# bluetooth_version_2.net
KiCad netlist of a schematic drawn in EAGLE
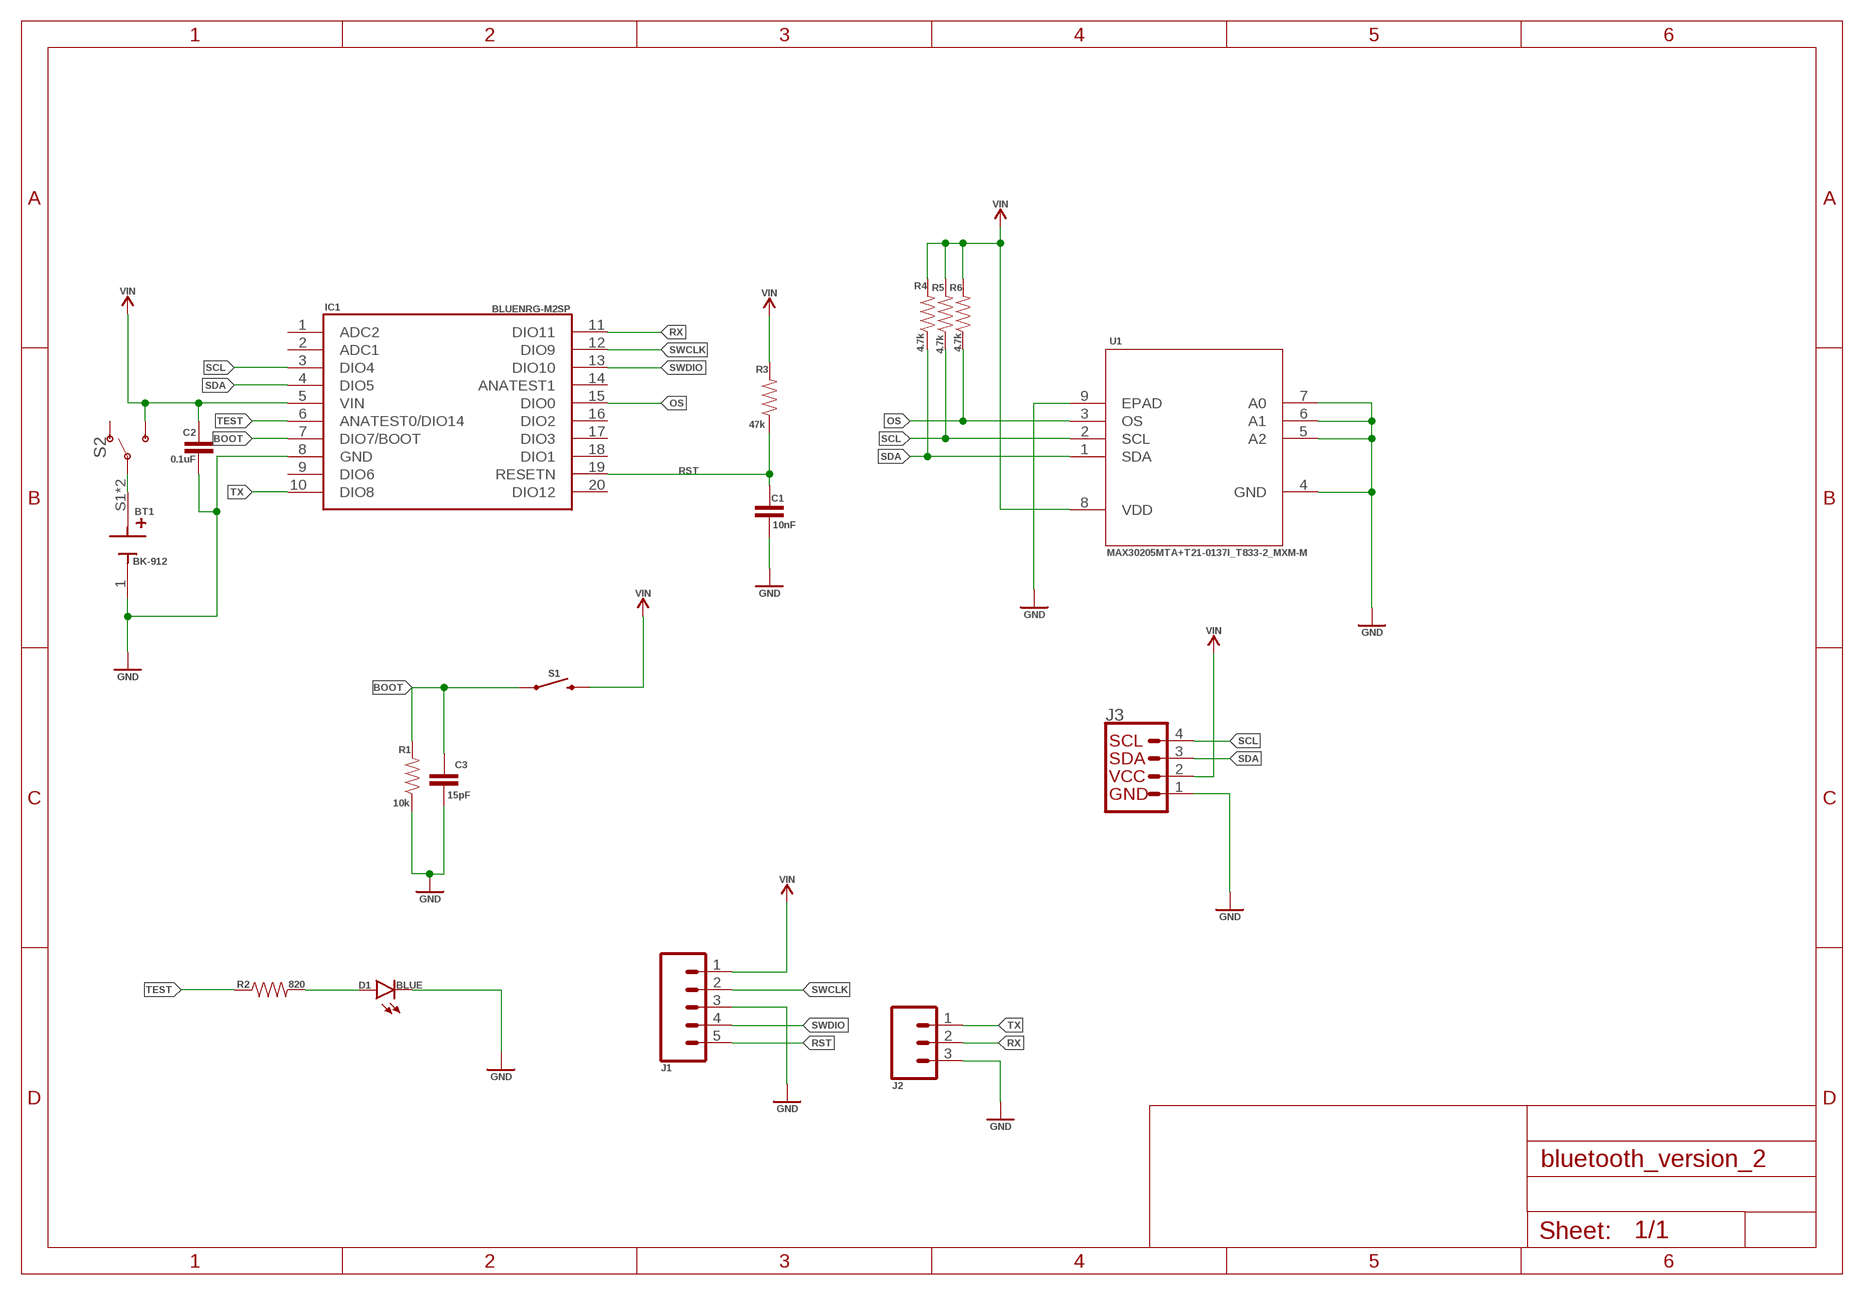
[diagram p0: schematic, sheet 1]

(export (version "E")
  (design (tool "Eeschema 10.0.6"))
  (components
    (comp (ref "BT1")
      (value "BK-912")
      (footprint "eagle-import:BAT_BK-912")
      (fields (field (name "MF") "MPD (Memory"))
      (libsource (lib "eagle-import") (part "BK-912"))
    )
    (comp (ref "C1")
      (value "10nF")
      (footprint "eagle-import:0603")
      (libsource (lib "eagle-import") (part "10NF-0603-50V-10%"))
    )
    (comp (ref "C2")
      (value "0.1uF")
      (footprint "eagle-import:0603")
      (libsource (lib "eagle-import") (part "0.1UF-0603-25V-(+80/-20%)"))
    )
    (comp (ref "C3")
      (value "15pF")
      (footprint "eagle-import:0603")
      (libsource (lib "eagle-import") (part "15PF-0603-50V-5%"))
    )
    (comp (ref "D1")
      (value "BLUE")
      (footprint "eagle-import:LED-0603")
      (libsource (lib "eagle-import") (part "LED-BLUE0603"))
    )
    (comp (ref "IC1")
      (value "BLUENRG-M2SP")
      (footprint "eagle-import:BLUENRGM2SP")
      (fields (field (name "MOUSER_PART_NUMBER") "511-BLUENRG-M2SP"))
      (libsource (lib "eagle-import") (part "BLUENRG-M2SP"))
    )
    (comp (ref "J1")
      (value "CONN_05")
      (footprint "eagle-import:1X05")
      (libsource (lib "eagle-import") (part "CONN_05"))
    )
    (comp (ref "J2")
      (value "455-1750-1-ND")
      (footprint "eagle-import:1X03")
      (libsource (lib "eagle-import") (part "CONN_03"))
    )
    (comp (ref "J3")
      (value "I2C_STANDARD")
      (footprint "eagle-import:1X04")
      (libsource (lib "eagle-import") (part "I2C_STANDARD"))
    )
    (comp (ref "R1")
      (value "10k")
      (footprint "eagle-import:0603")
      (libsource (lib "eagle-import") (part "10KOHM-0603-1/10W-1%"))
    )
    (comp (ref "R2")
      (value "820")
      (footprint "eagle-import:0603")
      (fields (field (name "SPICEPREFIX") "R"))
      (libsource (lib "eagle-import") (part "8.2KOHM-0603-1/10W-5%"))
    )
    (comp (ref "R3")
      (value "47k")
      (footprint "eagle-import:0603")
      (libsource (lib "eagle-import") (part "47KOHM-0603-1/10W-1%"))
    )
    (comp (ref "R4")
      (value "4.7k")
      (footprint "eagle-import:0603")
      (libsource (lib "eagle-import") (part "4.7KOHM-0603-1/10W-1%"))
    )
    (comp (ref "R5")
      (value "4.7k")
      (footprint "eagle-import:0603")
      (libsource (lib "eagle-import") (part "4.7KOHM-0603-1/10W-1%"))
    )
    (comp (ref "R6")
      (value "4.7k")
      (footprint "eagle-import:0603")
      (libsource (lib "eagle-import") (part "4.7KOHM-0603-1/10W-1%"))
    )
    (comp (ref "S1")
      (value "MOMENTARY-SWITCH-SPST-SMD-4.6X2.8MM")
      (footprint "eagle-import:TACTILE_SWITCH_SMD_4.6X2.8MM")
      (libsource (lib "eagle-import") (part "MOMENTARY-SWITCH-SPST-SMD-4.6X2.8MM"))
    )
    (comp (ref "S2")
      (value "SWITCH-SPDT-SMD-RIGHT-ANGLE")
      (footprint "eagle-import:SWITCH_SPST_SMD_A")
      (libsource (lib "eagle-import") (part "SWITCH-SPDT-SMD-RIGHT-ANGLE"))
    )
    (comp (ref "U1")
      (value "MAX30205MTA+T21-0137I_T833-2_MXM-M")
      (footprint "eagle-import:21-0137I_T833-2_MXM-M")
      (fields
        (field (name "MANUFACTURER_PART_NUMBER") "MAX30205MTA+T")
        (field (name "COPYRIGHT") "Copyright (C) 2018 Accelerated Designs. All rights reserved")
      )
      (libsource (lib "eagle-import") (part "MAX30205MTA+T21-0137I_T833-2_MXM-M"))
    )
  )
  (nets
    (net (code "1") (name "BOOT") (class "Default")
      (node (ref "C3") (pin "1") (pinfunction "1_1") (pintype "passive"))
      (node (ref "IC1") (pin "7") (pinfunction "DIO7/BOOT_7") (pintype "bidirectional"))
      (node (ref "R1") (pin "2") (pinfunction "2_2") (pintype "passive"))
      (node (ref "S1") (pin "1") (pinfunction "1_1") (pintype "passive"))
      (node (ref "S1") (pin "2") (pinfunction "1_2") (pintype "passive"))
    )
    (net (code "2") (name "GND") (class "Default")
      (node (ref "BT1") (pin "1") (pinfunction "-_1") (pintype "passive"))
      (node (ref "C1") (pin "2") (pinfunction "2_2") (pintype "passive"))
      (node (ref "C2") (pin "2") (pinfunction "2_2") (pintype "passive"))
      (node (ref "C3") (pin "2") (pinfunction "2_2") (pintype "passive"))
      (node (ref "D1") (pin "C") (pinfunction "C_C") (pintype "passive"))
      (node (ref "IC1") (pin "8") (pinfunction "GND_8") (pintype "bidirectional"))
      (node (ref "J1") (pin "3") (pinfunction "3_3") (pintype "passive"))
      (node (ref "J2") (pin "3") (pinfunction "3_3") (pintype "passive"))
      (node (ref "J3") (pin "1") (pinfunction "1_1") (pintype "power_in"))
      (node (ref "R1") (pin "1") (pinfunction "1_1") (pintype "passive"))
      (node (ref "U1") (pin "4") (pinfunction "GND_4") (pintype "passive"))
      (node (ref "U1") (pin "5") (pinfunction "A2_5") (pintype "bidirectional"))
      (node (ref "U1") (pin "6") (pinfunction "A1_6") (pintype "bidirectional"))
      (node (ref "U1") (pin "7") (pinfunction "A0_7") (pintype "bidirectional"))
      (node (ref "U1") (pin "9") (pinfunction "EPAD_9") (pintype "passive"))
    )
    (net (code "3") (name "Net-(D1-PadA)") (class "Default")
      (node (ref "D1") (pin "A") (pinfunction "A_A") (pintype "passive"))
      (node (ref "R2") (pin "2") (pinfunction "2_2") (pintype "passive"))
    )
    (net (code "4") (name "Net-(S2-P)") (class "Default")
      (node (ref "BT1") (pin "S1") (pinfunction "+_S1") (pintype "passive"))
      (node (ref "BT1") (pin "S2") (pinfunction "+_S2") (pintype "passive"))
      (node (ref "S2") (pin "2") (pinfunction "P_2") (pintype "passive"))
    )
    (net (code "5") (name "OS") (class "Default")
      (node (ref "IC1") (pin "15") (pinfunction "DIO0_15") (pintype "bidirectional"))
      (node (ref "R6") (pin "1") (pinfunction "1_1") (pintype "passive"))
      (node (ref "U1") (pin "3") (pinfunction "OS_3") (pintype "passive"))
    )
    (net (code "6") (name "RST") (class "Default")
      (node (ref "C1") (pin "1") (pinfunction "1_1") (pintype "passive"))
      (node (ref "IC1") (pin "19") (pinfunction "RESETN_19") (pintype "bidirectional"))
      (node (ref "J1") (pin "5") (pinfunction "5_5") (pintype "passive"))
      (node (ref "R3") (pin "1") (pinfunction "1_1") (pintype "passive"))
    )
    (net (code "7") (name "RX") (class "Default")
      (node (ref "IC1") (pin "11") (pinfunction "DIO11_11") (pintype "bidirectional"))
      (node (ref "J2") (pin "2") (pinfunction "2_2") (pintype "passive"))
    )
    (net (code "8") (name "SCL") (class "Default")
      (node (ref "IC1") (pin "3") (pinfunction "DIO4_3") (pintype "bidirectional"))
      (node (ref "J3") (pin "4") (pinfunction "4_4") (pintype "passive"))
      (node (ref "R5") (pin "1") (pinfunction "1_1") (pintype "passive"))
      (node (ref "U1") (pin "2") (pinfunction "SCL_2") (pintype "passive"))
    )
    (net (code "9") (name "SDA") (class "Default")
      (node (ref "IC1") (pin "4") (pinfunction "DIO5_4") (pintype "bidirectional"))
      (node (ref "J3") (pin "3") (pinfunction "3_3") (pintype "passive"))
      (node (ref "R4") (pin "1") (pinfunction "1_1") (pintype "passive"))
      (node (ref "U1") (pin "1") (pinfunction "SDA_1") (pintype "passive"))
    )
    (net (code "10") (name "SWCLK") (class "Default")
      (node (ref "IC1") (pin "12") (pinfunction "DIO9_12") (pintype "bidirectional"))
      (node (ref "J1") (pin "2") (pinfunction "2_2") (pintype "passive"))
    )
    (net (code "11") (name "SWDIO") (class "Default")
      (node (ref "IC1") (pin "13") (pinfunction "DIO10_13") (pintype "bidirectional"))
      (node (ref "J1") (pin "4") (pinfunction "4_4") (pintype "passive"))
    )
    (net (code "12") (name "TEST") (class "Default")
      (node (ref "IC1") (pin "6") (pinfunction "ANATEST0/DIO14_6") (pintype "bidirectional"))
      (node (ref "R2") (pin "1") (pinfunction "1_1") (pintype "passive"))
    )
    (net (code "13") (name "TX") (class "Default")
      (node (ref "IC1") (pin "10") (pinfunction "DIO8_10") (pintype "bidirectional"))
      (node (ref "J2") (pin "1") (pinfunction "1_1") (pintype "passive"))
    )
    (net (code "14") (name "VIN") (class "Default")
      (node (ref "C2") (pin "1") (pinfunction "1_1") (pintype "passive"))
      (node (ref "IC1") (pin "5") (pinfunction "VIN_5") (pintype "bidirectional"))
      (node (ref "J1") (pin "1") (pinfunction "1_1") (pintype "passive"))
      (node (ref "J3") (pin "2") (pinfunction "2_2") (pintype "power_in"))
      (node (ref "R3") (pin "2") (pinfunction "2_2") (pintype "passive"))
      (node (ref "R4") (pin "2") (pinfunction "2_2") (pintype "passive"))
      (node (ref "R5") (pin "2") (pinfunction "2_2") (pintype "passive"))
      (node (ref "R6") (pin "2") (pinfunction "2_2") (pintype "passive"))
      (node (ref "S1") (pin "3") (pinfunction "2_3") (pintype "passive"))
      (node (ref "S1") (pin "4") (pinfunction "2_4") (pintype "passive"))
      (node (ref "S2") (pin "3") (pinfunction "S_3") (pintype "passive"))
      (node (ref "U1") (pin "8") (pinfunction "VDD_8") (pintype "power_in"))
    )
    (net (code "15") (name "unconnected-(IC1-ADC1-Pad2)") (class "Default")
      (node (ref "IC1") (pin "2") (pinfunction "ADC1_2") (pintype "bidirectional"))
    )
    (net (code "16") (name "unconnected-(IC1-ADC2-Pad1)") (class "Default")
      (node (ref "IC1") (pin "1") (pinfunction "ADC2_1") (pintype "bidirectional"))
    )
    (net (code "17") (name "unconnected-(IC1-ANATEST1-Pad14)") (class "Default")
      (node (ref "IC1") (pin "14") (pinfunction "ANATEST1_14") (pintype "bidirectional"))
    )
    (net (code "18") (name "unconnected-(IC1-DIO1-Pad18)") (class "Default")
      (node (ref "IC1") (pin "18") (pinfunction "DIO1_18") (pintype "bidirectional"))
    )
    (net (code "19") (name "unconnected-(IC1-DIO2-Pad16)") (class "Default")
      (node (ref "IC1") (pin "16") (pinfunction "DIO2_16") (pintype "bidirectional"))
    )
    (net (code "20") (name "unconnected-(IC1-DIO3-Pad17)") (class "Default")
      (node (ref "IC1") (pin "17") (pinfunction "DIO3_17") (pintype "bidirectional"))
    )
    (net (code "21") (name "unconnected-(IC1-DIO6-Pad9)") (class "Default")
      (node (ref "IC1") (pin "9") (pinfunction "DIO6_9") (pintype "bidirectional"))
    )
    (net (code "22") (name "unconnected-(IC1-DIO12-Pad20)") (class "Default")
      (node (ref "IC1") (pin "20") (pinfunction "DIO12_20") (pintype "bidirectional"))
    )
    (net (code "23") (name "unconnected-(S2-O-Pad1)") (class "Default")
      (node (ref "S2") (pin "1") (pinfunction "O_1") (pintype "passive"))
    )
  )
)
